# sb-sonata-microsd.net
KiCad netlist of a schematic drawn in Altium Designer
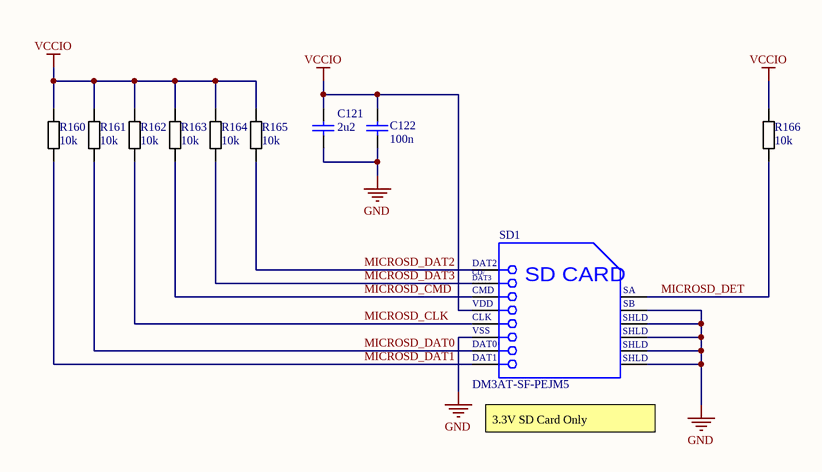
[diagram p0: sb-sonata-microsd.SchDoc]

(export (version "E")
  (design (tool "Eeschema 10.0.6"))
  (components
    (comp (ref "C121")
      (value "2u2")
      (footprint "CAPC0603_M")
      (description "2u2, 0603")
      (fields (field (name "PART NUMBER") "CCHIP-2u2-0603"))
      (libsource (lib "NewAE_AltiumLib") (part "CAP"))
    )
    (comp (ref "C122")
      (value "100n")
      (footprint "CAPC0402_M")
      (description "100n, 0402")
      (fields (field (name "PART NUMBER") "CCHIP-100n-0402"))
      (libsource (lib "NewAE_AltiumLib") (part "CAP"))
    )
    (comp (ref "R160")
      (value "10k")
      (footprint "RESC1005X40N")
      (description "10k res, 0402, 1%, 1/16W")
      (fields (field (name "PART NUMBER") "RCHIP-10K-0402") (field (name "TOLERANCE") "1%"))
      (libsource (lib "NewAE_AltiumLib") (part "RES-EU"))
    )
    (comp (ref "R161")
      (value "10k")
      (footprint "RESC1005X40N")
      (description "10k res, 0402, 1%, 1/16W")
      (fields (field (name "PART NUMBER") "RCHIP-10K-0402") (field (name "TOLERANCE") "1%"))
      (libsource (lib "NewAE_AltiumLib") (part "RES-EU"))
    )
    (comp (ref "R162")
      (value "10k")
      (footprint "RESC1005X40N")
      (description "10k res, 0402, 1%, 1/16W")
      (fields (field (name "PART NUMBER") "RCHIP-10K-0402") (field (name "TOLERANCE") "1%"))
      (libsource (lib "NewAE_AltiumLib") (part "RES-EU"))
    )
    (comp (ref "R163")
      (value "10k")
      (footprint "RESC1005X40N")
      (description "10k res, 0402, 1%, 1/16W")
      (fields (field (name "PART NUMBER") "RCHIP-10K-0402") (field (name "TOLERANCE") "1%"))
      (libsource (lib "NewAE_AltiumLib") (part "RES-EU"))
    )
    (comp (ref "R164")
      (value "10k")
      (footprint "RESC1005X40N")
      (description "10k res, 0402, 1%, 1/16W")
      (fields (field (name "PART NUMBER") "RCHIP-10K-0402") (field (name "TOLERANCE") "1%"))
      (libsource (lib "NewAE_AltiumLib") (part "RES-EU"))
    )
    (comp (ref "R165")
      (value "10k")
      (footprint "RESC1005X40N")
      (description "10k res, 0402, 1%, 1/16W")
      (fields (field (name "PART NUMBER") "RCHIP-10K-0402") (field (name "TOLERANCE") "1%"))
      (libsource (lib "NewAE_AltiumLib") (part "RES-EU"))
    )
    (comp (ref "R166")
      (value "10k")
      (footprint "RESC1005X40N")
      (description "10k res, 0402, 1%, 1/16W")
      (fields (field (name "PART NUMBER") "RCHIP-10K-0402") (field (name "TOLERANCE") "1%"))
      (libsource (lib "NewAE_AltiumLib") (part "RES-EU"))
    )
    (comp (ref "SD1")
      (value "DM3AT-SF-PEJM5")
      (footprint "FP-DM3AT-SF-PEJM5-MFG")
      (description "Micro SD Card Connector, 0.5 A, 125 V, -25 to 85 degC, 8-Pin SMD, RoHS, Tape and Reel")
      (fields (field (name "MANUFACTURER") "Hirose Electric"))
      (libsource (lib "Altium Content Vault") (part "CN-SD-8-2SW-4S_A"))
    )
  )
  (nets
    (net (code "1") (name "/MICROSD_CLK") (class "Default")
      (node (ref "R162") (pin "1") (pinfunction "1_1") (pintype "passive"))
      (node (ref "SD1") (pin "5") (pinfunction "CLK_5") (pintype "passive"))
    )
    (net (code "2") (name "/MICROSD_CMD") (class "Default")
      (node (ref "R163") (pin "1") (pinfunction "1_1") (pintype "passive"))
      (node (ref "SD1") (pin "3") (pinfunction "CMD_3") (pintype "passive"))
    )
    (net (code "3") (name "/MICROSD_DAT0") (class "Default")
      (node (ref "R161") (pin "1") (pinfunction "1_1") (pintype "passive"))
      (node (ref "SD1") (pin "7") (pinfunction "DAT0_7") (pintype "passive"))
    )
    (net (code "4") (name "/MICROSD_DAT1") (class "Default")
      (node (ref "R160") (pin "1") (pinfunction "1_1") (pintype "passive"))
      (node (ref "SD1") (pin "8") (pinfunction "DAT1_8") (pintype "passive"))
    )
    (net (code "5") (name "/MICROSD_DAT2") (class "Default")
      (node (ref "R165") (pin "1") (pinfunction "1_1") (pintype "passive"))
      (node (ref "SD1") (pin "1") (pinfunction "DAT2_1") (pintype "passive"))
    )
    (net (code "6") (name "/MICROSD_DAT3") (class "Default")
      (node (ref "R164") (pin "1") (pinfunction "1_1") (pintype "passive"))
      (node (ref "SD1") (pin "2") (pinfunction "CD/DAT3_2") (pintype "passive"))
    )
    (net (code "7") (name "/MICROSD_DET") (class "Default")
      (node (ref "R166") (pin "1") (pinfunction "1_1") (pintype "passive"))
      (node (ref "SD1") (pin "9") (pinfunction "SA_9") (pintype "passive"))
    )
    (net (code "8") (name "GND") (class "Default")
      (node (ref "C121") (pin "2") (pinfunction "2_2") (pintype "passive"))
      (node (ref "C122") (pin "2") (pinfunction "2_2") (pintype "passive"))
      (node (ref "SD1") (pin "10") (pinfunction "SB_10") (pintype "passive"))
      (node (ref "SD1") (pin "11") (pinfunction "SHLD_11") (pintype "passive"))
      (node (ref "SD1") (pin "12") (pinfunction "SHLD_12") (pintype "passive"))
      (node (ref "SD1") (pin "13") (pinfunction "SHLD_13") (pintype "passive"))
      (node (ref "SD1") (pin "14") (pinfunction "SHLD_14") (pintype "passive"))
      (node (ref "SD1") (pin "6") (pinfunction "VSS_6") (pintype "passive"))
    )
    (net (code "9") (name "VCCIO") (class "Default")
      (node (ref "C121") (pin "1") (pinfunction "1_1") (pintype "passive"))
      (node (ref "C122") (pin "1") (pinfunction "1_1") (pintype "passive"))
      (node (ref "R160") (pin "2") (pinfunction "2_2") (pintype "passive"))
      (node (ref "R161") (pin "2") (pinfunction "2_2") (pintype "passive"))
      (node (ref "R162") (pin "2") (pinfunction "2_2") (pintype "passive"))
      (node (ref "R163") (pin "2") (pinfunction "2_2") (pintype "passive"))
      (node (ref "R164") (pin "2") (pinfunction "2_2") (pintype "passive"))
      (node (ref "R165") (pin "2") (pinfunction "2_2") (pintype "passive"))
      (node (ref "R166") (pin "2") (pinfunction "2_2") (pintype "passive"))
      (node (ref "SD1") (pin "4") (pinfunction "VDD_4") (pintype "passive"))
    )
  )
)
